# SCH_555-Circuit_2025-10-19.net
KiCad netlist of a schematic drawn in EasyEDA
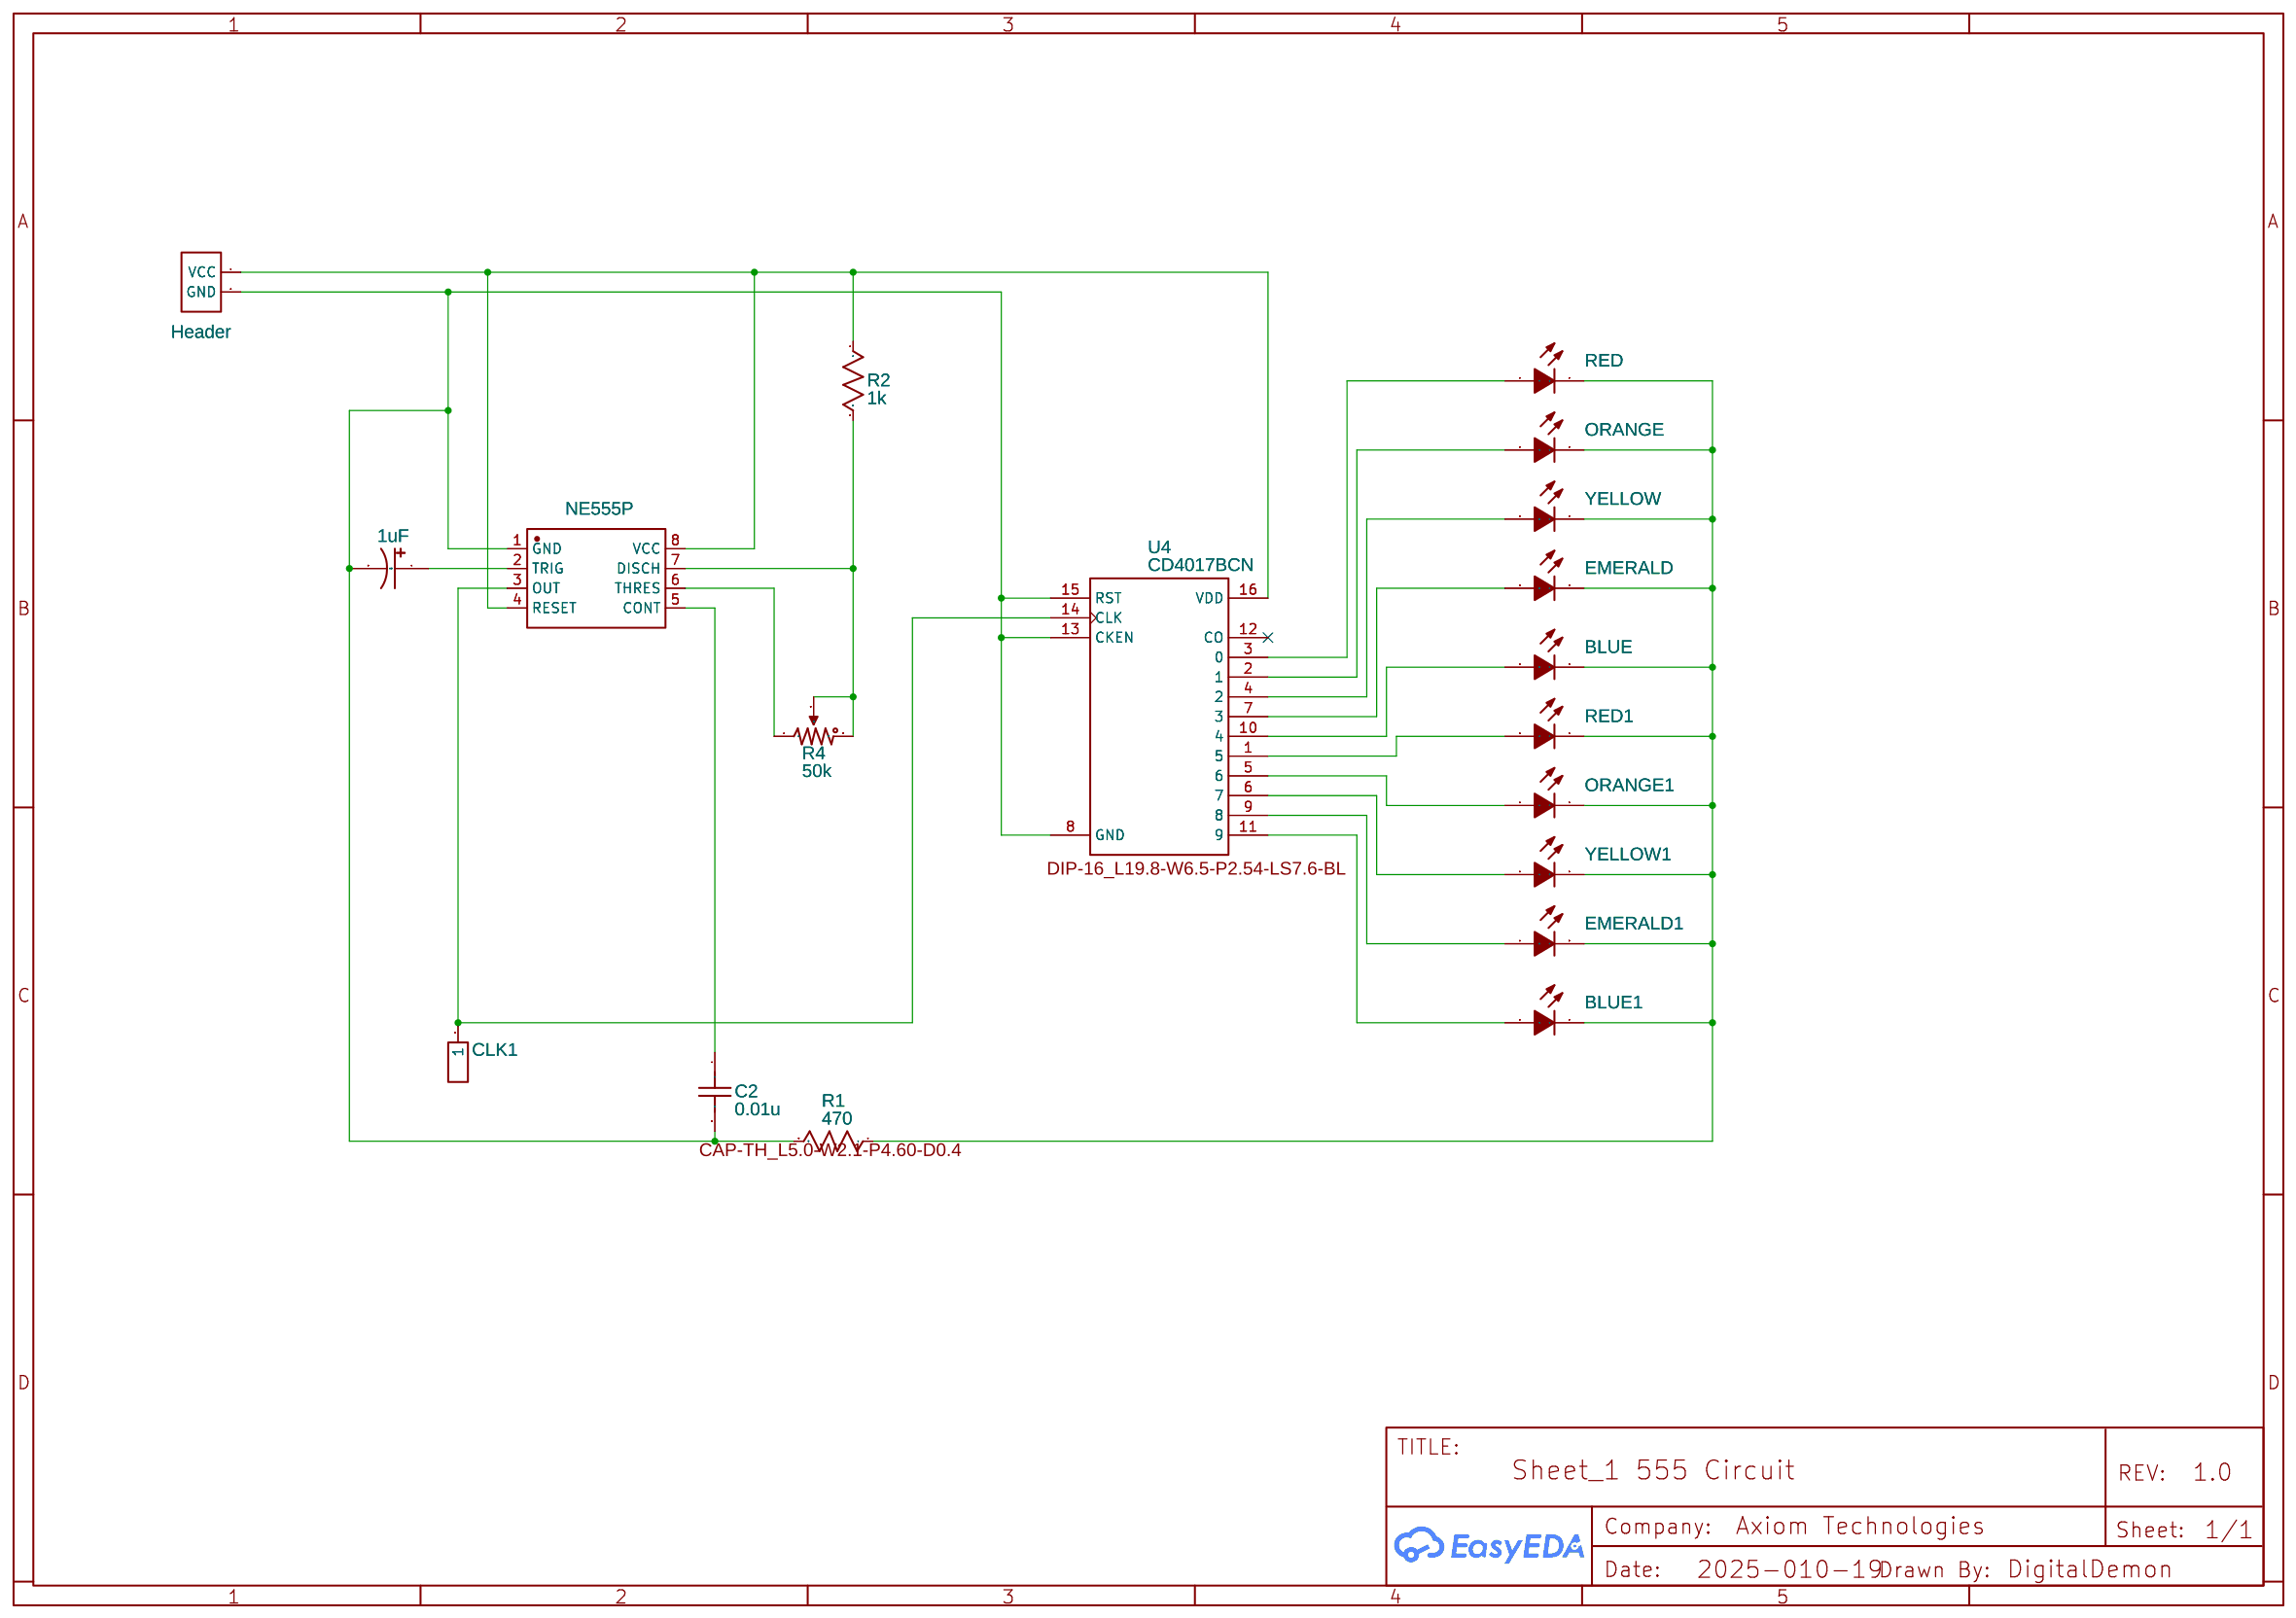
[diagram p0: schematic sheet]

(export (version "E")
  (design (tool "Eeschema 10.0.6"))
  (components
    (comp (ref "BLUE") (value "LED_5MM") (libsource (lib "") (part "LED_5MM_3")))
    (comp (ref "BLUE1") (value "LED_5MM") (libsource (lib "") (part "LED_5MM_3")))
    (comp (ref "C1")
      (value "1uF")
      (fields (field (name "Manufacturer Part") "UVZ1H010MDD") (field (name "Manufacturer") "Nichicon(尼吉康)"))
      (libsource (lib "") (part "UVZ1H010MDD"))
    )
    (comp (ref "C2") (value "0.01u") (libsource (lib "") (part "C_0603_US")))
    (comp (ref "CLK1")
      (value "C81276")
      (fields
        (field (name "Manufacturer Part") "2.54-1*1P针")
        (field (name "Manufacturer") "BOOMELE(Boom Precision Elec)")
      )
      (libsource (lib "") (part "Header-Male-2.54_1x1"))
    )
    (comp (ref "EMERALD") (value "LED_5MM") (libsource (lib "") (part "LED_5MM_1")))
    (comp (ref "EMERALD1") (value "LED_5MM") (libsource (lib "") (part "LED_5MM_1")))
    (comp (ref "H1") (value "Header") (libsource (lib "") (part "HEADER-FEMALE-2.54_1X2")))
    (comp (ref "ORANGE") (value "LED_5MM") (libsource (lib "") (part "LED_5MM")))
    (comp (ref "ORANGE1") (value "LED_5MM") (libsource (lib "") (part "LED_5MM")))
    (comp (ref "R1")
      (value "470")
      (fields (field (name "Manufacturer Part") "?"))
      (libsource (lib "") (part "Resistor_1"))
    )
    (comp (ref "R2")
      (value "1k")
      (fields (field (name "Manufacturer Part") "?"))
      (libsource (lib "") (part "Resistor"))
    )
    (comp (ref "R4")
      (value "50k")
      (fields (field (name "Manufacturer Part") "?"))
      (libsource (lib "") (part "Potentiometer"))
    )
    (comp (ref "RED") (value "LED_5MM") (libsource (lib "") (part "LED_5MM_4")))
    (comp (ref "RED1") (value "LED_5MM") (libsource (lib "") (part "LED_5MM_4")))
    (comp (ref "U2")
      (value "NE555P")
      (fields (field (name "Manufacturer") "TI(德州仪器)"))
      (libsource (lib "") (part "NE555P"))
    )
    (comp (ref "U4") (value "CD4017BCN") (libsource (lib "") (part "CD4017BCN")))
    (comp (ref "YELLOW") (value "LED_5MM") (libsource (lib "") (part "LED_5MM_2")))
    (comp (ref "YELLOW1") (value "LED_5MM") (libsource (lib "") (part "LED_5MM_2")))
  )
  (nets
    (net (code "1") (name "Net-(BLUE-A)") (class "Default")
      (node (ref "BLUE") (pin "1") (pinfunction "A_1") (pintype "input"))
      (node (ref "U4") (pin "10") (pinfunction "4_10") (pintype "output"))
    )
    (net (code "2") (name "Net-(BLUE-K)") (class "Default")
      (node (ref "BLUE") (pin "2") (pinfunction "K_2") (pintype "input"))
      (node (ref "BLUE1") (pin "2") (pinfunction "K_2") (pintype "input"))
      (node (ref "EMERALD") (pin "2") (pinfunction "K_2") (pintype "input"))
      (node (ref "EMERALD1") (pin "2") (pinfunction "K_2") (pintype "input"))
      (node (ref "ORANGE") (pin "2") (pinfunction "K_2") (pintype "input"))
      (node (ref "ORANGE1") (pin "2") (pinfunction "K_2") (pintype "input"))
      (node (ref "R1") (pin "1") (pinfunction "1_1") (pintype "unspecified"))
      (node (ref "RED") (pin "2") (pinfunction "K_2") (pintype "input"))
      (node (ref "RED1") (pin "2") (pinfunction "K_2") (pintype "input"))
      (node (ref "YELLOW") (pin "2") (pinfunction "K_2") (pintype "input"))
      (node (ref "YELLOW1") (pin "2") (pinfunction "K_2") (pintype "input"))
    )
    (net (code "3") (name "Net-(BLUE1-A)") (class "Default")
      (node (ref "BLUE1") (pin "1") (pinfunction "A_1") (pintype "input"))
      (node (ref "U4") (pin "11") (pinfunction "9_11") (pintype "output"))
    )
    (net (code "4") (name "Net-(EMERALD-A)") (class "Default")
      (node (ref "EMERALD") (pin "1") (pinfunction "A_1") (pintype "input"))
      (node (ref "U4") (pin "7") (pinfunction "3_7") (pintype "output"))
    )
    (net (code "5") (name "Net-(EMERALD1-A)") (class "Default")
      (node (ref "EMERALD1") (pin "1") (pinfunction "A_1") (pintype "input"))
      (node (ref "U4") (pin "9") (pinfunction "8_9") (pintype "output"))
    )
    (net (code "6") (name "Net-(H1-GND)") (class "Default")
      (node (ref "C1") (pin "2") (pinfunction "2_2") (pintype "unspecified"))
      (node (ref "C2") (pin "2") (pinfunction "2_2") (pintype "unspecified"))
      (node (ref "H1") (pin "2") (pinfunction "GND_2") (pintype "unspecified"))
      (node (ref "R1") (pin "2") (pinfunction "2_2") (pintype "unspecified"))
      (node (ref "U2") (pin "1") (pinfunction "GND_1") (pintype "unspecified"))
      (node (ref "U4") (pin "13") (pinfunction "CKEN_13") (pintype "unspecified"))
      (node (ref "U4") (pin "15") (pinfunction "RST_15") (pintype "unspecified"))
      (node (ref "U4") (pin "8") (pinfunction "GND_8") (pintype "passive"))
    )
    (net (code "7") (name "Net-(H1-VCC)") (class "Default")
      (node (ref "H1") (pin "1") (pinfunction "VCC_1") (pintype "unspecified"))
      (node (ref "R2") (pin "1") (pinfunction "1_1") (pintype "unspecified"))
      (node (ref "U2") (pin "4") (pinfunction "RESET_4") (pintype "unspecified"))
      (node (ref "U2") (pin "8") (pinfunction "VCC_8") (pintype "unspecified"))
      (node (ref "U4") (pin "16") (pinfunction "VDD_16") (pintype "passive"))
    )
    (net (code "8") (name "Net-(ORANGE-A)") (class "Default")
      (node (ref "ORANGE") (pin "1") (pinfunction "A_1") (pintype "input"))
      (node (ref "U4") (pin "2") (pinfunction "1_2") (pintype "output"))
    )
    (net (code "9") (name "Net-(ORANGE1-A)") (class "Default")
      (node (ref "ORANGE1") (pin "1") (pinfunction "A_1") (pintype "input"))
      (node (ref "U4") (pin "5") (pinfunction "6_5") (pintype "output"))
    )
    (net (code "10") (name "Net-(R4-2)") (class "Default")
      (node (ref "R2") (pin "2") (pinfunction "2_2") (pintype "unspecified"))
      (node (ref "R4") (pin "2") (pinfunction "3_2") (pintype "unspecified"))
      (node (ref "R4") (pin "3") (pinfunction "2_3") (pintype "unspecified"))
      (node (ref "U2") (pin "7") (pinfunction "DISCH_7") (pintype "unspecified"))
    )
    (net (code "11") (name "Net-(RED-A)") (class "Default")
      (node (ref "RED") (pin "1") (pinfunction "A_1") (pintype "input"))
      (node (ref "U4") (pin "3") (pinfunction "0_3") (pintype "output"))
    )
    (net (code "12") (name "Net-(RED1-A)") (class "Default")
      (node (ref "RED1") (pin "1") (pinfunction "A_1") (pintype "input"))
      (node (ref "U4") (pin "1") (pinfunction "5_1") (pintype "output"))
    )
    (net (code "13") (name "Net-(U2-CONT)") (class "Default")
      (node (ref "C2") (pin "1") (pinfunction "1_1") (pintype "unspecified"))
      (node (ref "U2") (pin "5") (pinfunction "CONT_5") (pintype "unspecified"))
    )
    (net (code "14") (name "Net-(U2-OUT)") (class "Default")
      (node (ref "CLK1") (pin "1") (pinfunction "1_1") (pintype "unspecified"))
      (node (ref "U2") (pin "3") (pinfunction "OUT_3") (pintype "unspecified"))
      (node (ref "U4") (pin "14") (pinfunction "CLK_14") (pintype "unspecified"))
    )
    (net (code "15") (name "Net-(U2-THRES)") (class "Default")
      (node (ref "R4") (pin "1") (pinfunction "1_1") (pintype "unspecified"))
      (node (ref "U2") (pin "6") (pinfunction "THRES_6") (pintype "unspecified"))
    )
    (net (code "16") (name "Net-(U2-TRIG)") (class "Default")
      (node (ref "C1") (pin "1") (pinfunction "1_1") (pintype "unspecified"))
      (node (ref "U2") (pin "2") (pinfunction "TRIG_2") (pintype "unspecified"))
    )
    (net (code "17") (name "Net-(U4-2)") (class "Default")
      (node (ref "U4") (pin "4") (pinfunction "2_4") (pintype "output"))
      (node (ref "YELLOW") (pin "1") (pinfunction "A_1") (pintype "input"))
    )
    (net (code "18") (name "Net-(U4-7)") (class "Default")
      (node (ref "U4") (pin "6") (pinfunction "7_6") (pintype "output"))
      (node (ref "YELLOW1") (pin "1") (pinfunction "A_1") (pintype "input"))
    )
    (net (code "19") (name "unconnected-(U4-CO-Pad12)") (class "Default")
      (node (ref "U4") (pin "12") (pinfunction "CO_12") (pintype "output+no_connect"))
    )
  )
)
